# DACCACCHE_ERRARD_Schematic.net
KiCad netlist of a schematic drawn in EAGLE
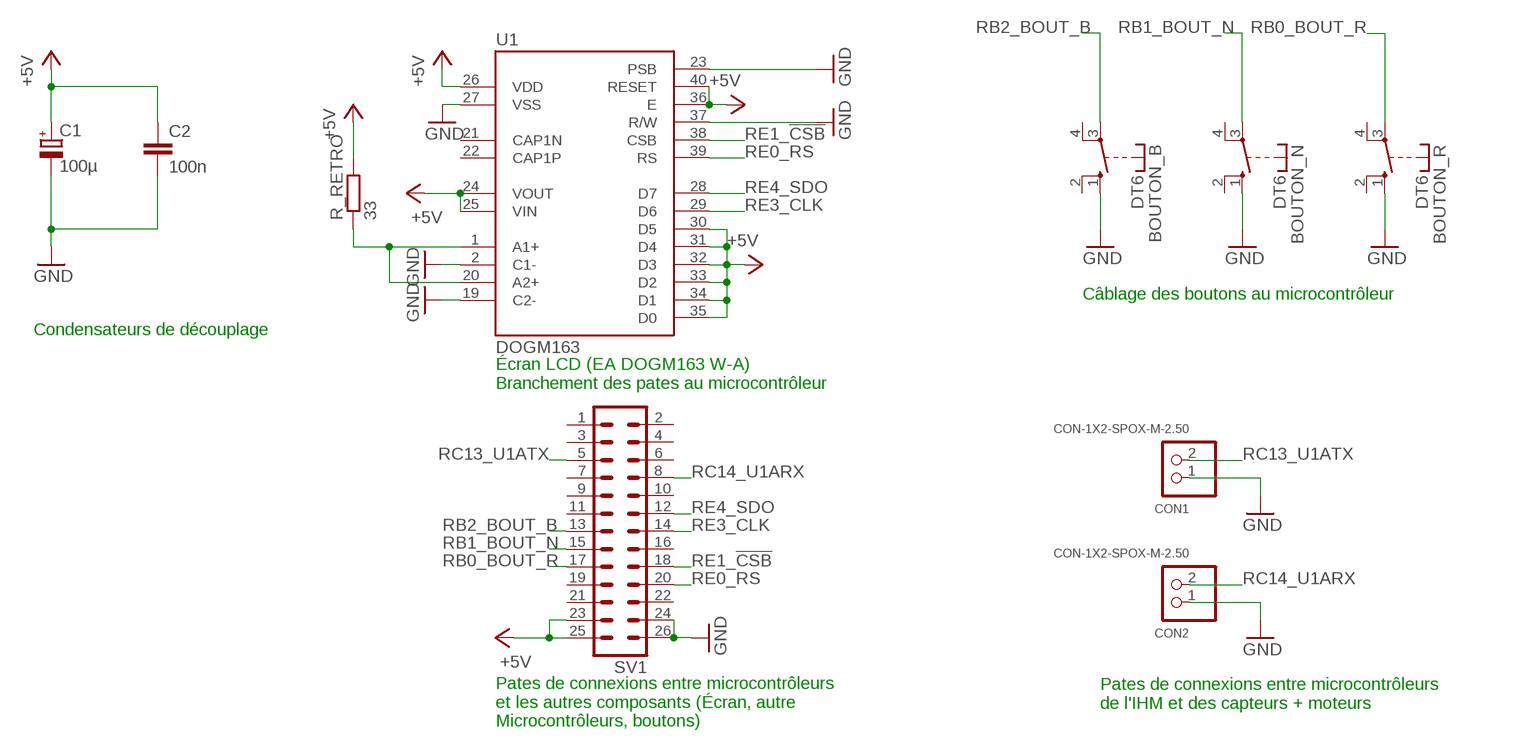
[diagram p0: schematic, sheet 1]

(export (version "E")
  (design (tool "Eeschema 10.0.6"))
  (components
    (comp (ref "BOUTON_B")
      (value "DT6")
      (footprint "eagle-import:DT6")
      (libsource (lib "eagle-import") (part "DT6"))
    )
    (comp (ref "BOUTON_N")
      (value "DT6")
      (footprint "eagle-import:DT6")
      (libsource (lib "eagle-import") (part "DT6"))
    )
    (comp (ref "BOUTON_R")
      (value "DT6")
      (footprint "eagle-import:DT6")
      (libsource (lib "eagle-import") (part "DT6"))
    )
    (comp (ref "C1")
      (value "100µ")
      (footprint "eagle-import:E2,5-7")
      (libsource (lib "eagle-import") (part "CPOL-EUE2.5-7"))
    )
    (comp (ref "C2")
      (value "100n")
      (footprint "eagle-import:C025-025X050")
      (libsource (lib "eagle-import") (part "C-EU025-025X050"))
    )
    (comp (ref "CON1")
      (value "CON-1X2-SPOX-M-2.50")
      (footprint "eagle-import:SPOX-M-2.50-02")
      (libsource (lib "eagle-import") (part "CON-1X2-SPOX-M-2.50"))
    )
    (comp (ref "CON2")
      (value "CON-1X2-SPOX-M-2.50")
      (footprint "eagle-import:SPOX-M-2.50-02")
      (libsource (lib "eagle-import") (part "CON-1X2-SPOX-M-2.50"))
    )
    (comp (ref "R_RETRO")
      (value "33")
      (footprint "eagle-import:0207_15")
      (libsource (lib "eagle-import") (part "R-EU_0207/15"))
    )
    (comp (ref "SV1")
      (value "ML26")
      (footprint "eagle-import:ML26")
      (libsource (lib "eagle-import") (part "ML26"))
    )
    (comp (ref "U1")
      (value "DOGM163")
      (footprint "eagle-import:DOGM")
      (libsource (lib "eagle-import") (part "DOGM163"))
    )
  )
  (nets
    (net (code "1") (name "+5V") (class "Default")
      (node (ref "C1") (pin "+") (pinfunction "+_+") (pintype "passive"))
      (node (ref "C2") (pin "1") (pinfunction "1_1") (pintype "passive"))
      (node (ref "R_RETRO") (pin "2") (pinfunction "2_2") (pintype "passive"))
      (node (ref "SV1") (pin "23") (pinfunction "23_23") (pintype "passive"))
      (node (ref "SV1") (pin "25") (pinfunction "25_25") (pintype "passive"))
      (node (ref "U1") (pin "24") (pinfunction "VOUT_24") (pintype "bidirectional"))
      (node (ref "U1") (pin "25") (pinfunction "VIN_25") (pintype "bidirectional"))
      (node (ref "U1") (pin "26") (pinfunction "VDD_26") (pintype "bidirectional"))
      (node (ref "U1") (pin "30") (pinfunction "D5_30") (pintype "bidirectional"))
      (node (ref "U1") (pin "31") (pinfunction "D4_31") (pintype "bidirectional"))
      (node (ref "U1") (pin "32") (pinfunction "D3_32") (pintype "bidirectional"))
      (node (ref "U1") (pin "33") (pinfunction "D2_33") (pintype "bidirectional"))
      (node (ref "U1") (pin "34") (pinfunction "D1_34") (pintype "bidirectional"))
      (node (ref "U1") (pin "35") (pinfunction "D0_35") (pintype "bidirectional"))
      (node (ref "U1") (pin "36") (pinfunction "E_36") (pintype "bidirectional"))
      (node (ref "U1") (pin "40") (pinfunction "RESET_40") (pintype "bidirectional"))
    )
    (net (code "2") (name "/RB0_BOUT_R") (class "Default")
      (node (ref "BOUTON_R") (pin "3") (pinfunction "P_3") (pintype "passive"))
      (node (ref "SV1") (pin "17") (pinfunction "17_17") (pintype "passive"))
    )
    (net (code "3") (name "/RB1_BOUT_N") (class "Default")
      (node (ref "BOUTON_N") (pin "3") (pinfunction "P_3") (pintype "passive"))
      (node (ref "SV1") (pin "15") (pinfunction "15_15") (pintype "passive"))
    )
    (net (code "4") (name "/RB2_BOUT_B") (class "Default")
      (node (ref "BOUTON_B") (pin "3") (pinfunction "P_3") (pintype "passive"))
      (node (ref "SV1") (pin "13") (pinfunction "13_13") (pintype "passive"))
    )
    (net (code "5") (name "/RC13_U1ATX") (class "Default")
      (node (ref "CON1") (pin "2") (pinfunction "2_2") (pintype "passive"))
      (node (ref "SV1") (pin "5") (pinfunction "5_5") (pintype "passive"))
    )
    (net (code "6") (name "/RC14_U1ARX") (class "Default")
      (node (ref "CON2") (pin "2") (pinfunction "2_2") (pintype "passive"))
      (node (ref "SV1") (pin "8") (pinfunction "8_8") (pintype "passive"))
    )
    (net (code "7") (name "/RE0_RS") (class "Default")
      (node (ref "SV1") (pin "20") (pinfunction "20_20") (pintype "passive"))
      (node (ref "U1") (pin "39") (pinfunction "RS_39") (pintype "bidirectional"))
    )
    (net (code "8") (name "/RE1_~{CSB}") (class "Default")
      (node (ref "SV1") (pin "18") (pinfunction "18_18") (pintype "passive"))
      (node (ref "U1") (pin "38") (pinfunction "CSB_38") (pintype "bidirectional"))
    )
    (net (code "9") (name "/RE3_CLK") (class "Default")
      (node (ref "SV1") (pin "14") (pinfunction "14_14") (pintype "passive"))
      (node (ref "U1") (pin "29") (pinfunction "D6_29") (pintype "bidirectional"))
    )
    (net (code "10") (name "/RE4_SDO") (class "Default")
      (node (ref "SV1") (pin "12") (pinfunction "12_12") (pintype "passive"))
      (node (ref "U1") (pin "28") (pinfunction "D7_28") (pintype "bidirectional"))
    )
    (net (code "11") (name "GND") (class "Default")
      (node (ref "BOUTON_B") (pin "1") (pinfunction "S_1") (pintype "passive"))
      (node (ref "BOUTON_N") (pin "1") (pinfunction "S_1") (pintype "passive"))
      (node (ref "BOUTON_R") (pin "1") (pinfunction "S_1") (pintype "passive"))
      (node (ref "C1") (pin "-") (pinfunction "-_-") (pintype "passive"))
      (node (ref "C2") (pin "2") (pinfunction "2_2") (pintype "passive"))
      (node (ref "CON1") (pin "1") (pinfunction "1_1") (pintype "passive"))
      (node (ref "CON2") (pin "1") (pinfunction "1_1") (pintype "passive"))
      (node (ref "SV1") (pin "24") (pinfunction "24_24") (pintype "passive"))
      (node (ref "SV1") (pin "26") (pinfunction "26_26") (pintype "passive"))
      (node (ref "U1") (pin "19") (pinfunction "C2-_19") (pintype "bidirectional"))
      (node (ref "U1") (pin "2") (pinfunction "C1-_2") (pintype "bidirectional"))
      (node (ref "U1") (pin "23") (pinfunction "PSB_23") (pintype "bidirectional"))
      (node (ref "U1") (pin "27") (pinfunction "VSS_27") (pintype "bidirectional"))
      (node (ref "U1") (pin "37") (pinfunction "R/W_37") (pintype "bidirectional"))
    )
    (net (code "12") (name "Net-(U1-A1+)") (class "Default")
      (node (ref "R_RETRO") (pin "1") (pinfunction "1_1") (pintype "passive"))
      (node (ref "U1") (pin "1") (pinfunction "A1+_1") (pintype "bidirectional"))
      (node (ref "U1") (pin "20") (pinfunction "A2+_20") (pintype "bidirectional"))
    )
    (net (code "13") (name "unconnected-(BOUTON_B-P-Pad4)") (class "Default")
      (node (ref "BOUTON_B") (pin "4") (pinfunction "P_4") (pintype "passive"))
    )
    (net (code "14") (name "unconnected-(BOUTON_B-S-Pad2)") (class "Default")
      (node (ref "BOUTON_B") (pin "2") (pinfunction "S_2") (pintype "passive"))
    )
    (net (code "15") (name "unconnected-(BOUTON_N-P-Pad4)") (class "Default")
      (node (ref "BOUTON_N") (pin "4") (pinfunction "P_4") (pintype "passive"))
    )
    (net (code "16") (name "unconnected-(BOUTON_N-S-Pad2)") (class "Default")
      (node (ref "BOUTON_N") (pin "2") (pinfunction "S_2") (pintype "passive"))
    )
    (net (code "17") (name "unconnected-(BOUTON_R-P-Pad4)") (class "Default")
      (node (ref "BOUTON_R") (pin "4") (pinfunction "P_4") (pintype "passive"))
    )
    (net (code "18") (name "unconnected-(BOUTON_R-S-Pad2)") (class "Default")
      (node (ref "BOUTON_R") (pin "2") (pinfunction "S_2") (pintype "passive"))
    )
    (net (code "19") (name "unconnected-(SV1-Pad1)") (class "Default")
      (node (ref "SV1") (pin "1") (pinfunction "1_1") (pintype "passive"))
    )
    (net (code "20") (name "unconnected-(SV1-Pad2)") (class "Default")
      (node (ref "SV1") (pin "2") (pinfunction "2_2") (pintype "passive"))
    )
    (net (code "21") (name "unconnected-(SV1-Pad3)") (class "Default")
      (node (ref "SV1") (pin "3") (pinfunction "3_3") (pintype "passive"))
    )
    (net (code "22") (name "unconnected-(SV1-Pad4)") (class "Default")
      (node (ref "SV1") (pin "4") (pinfunction "4_4") (pintype "passive"))
    )
    (net (code "23") (name "unconnected-(SV1-Pad6)") (class "Default")
      (node (ref "SV1") (pin "6") (pinfunction "6_6") (pintype "passive"))
    )
    (net (code "24") (name "unconnected-(SV1-Pad7)") (class "Default")
      (node (ref "SV1") (pin "7") (pinfunction "7_7") (pintype "passive"))
    )
    (net (code "25") (name "unconnected-(SV1-Pad9)") (class "Default")
      (node (ref "SV1") (pin "9") (pinfunction "9_9") (pintype "passive"))
    )
    (net (code "26") (name "unconnected-(SV1-Pad10)") (class "Default")
      (node (ref "SV1") (pin "10") (pinfunction "10_10") (pintype "passive"))
    )
    (net (code "27") (name "unconnected-(SV1-Pad11)") (class "Default")
      (node (ref "SV1") (pin "11") (pinfunction "11_11") (pintype "passive"))
    )
    (net (code "28") (name "unconnected-(SV1-Pad16)") (class "Default")
      (node (ref "SV1") (pin "16") (pinfunction "16_16") (pintype "passive"))
    )
    (net (code "29") (name "unconnected-(SV1-Pad19)") (class "Default")
      (node (ref "SV1") (pin "19") (pinfunction "19_19") (pintype "passive"))
    )
    (net (code "30") (name "unconnected-(SV1-Pad21)") (class "Default")
      (node (ref "SV1") (pin "21") (pinfunction "21_21") (pintype "passive"))
    )
    (net (code "31") (name "unconnected-(SV1-Pad22)") (class "Default")
      (node (ref "SV1") (pin "22") (pinfunction "22_22") (pintype "passive"))
    )
    (net (code "32") (name "unconnected-(U1-CAP1N-Pad21)") (class "Default")
      (node (ref "U1") (pin "21") (pinfunction "CAP1N_21") (pintype "bidirectional"))
    )
    (net (code "33") (name "unconnected-(U1-CAP1P-Pad22)") (class "Default")
      (node (ref "U1") (pin "22") (pinfunction "CAP1P_22") (pintype "bidirectional"))
    )
  )
)
